# amp_kit_v02.net
KiCad netlist of a schematic drawn in EAGLE
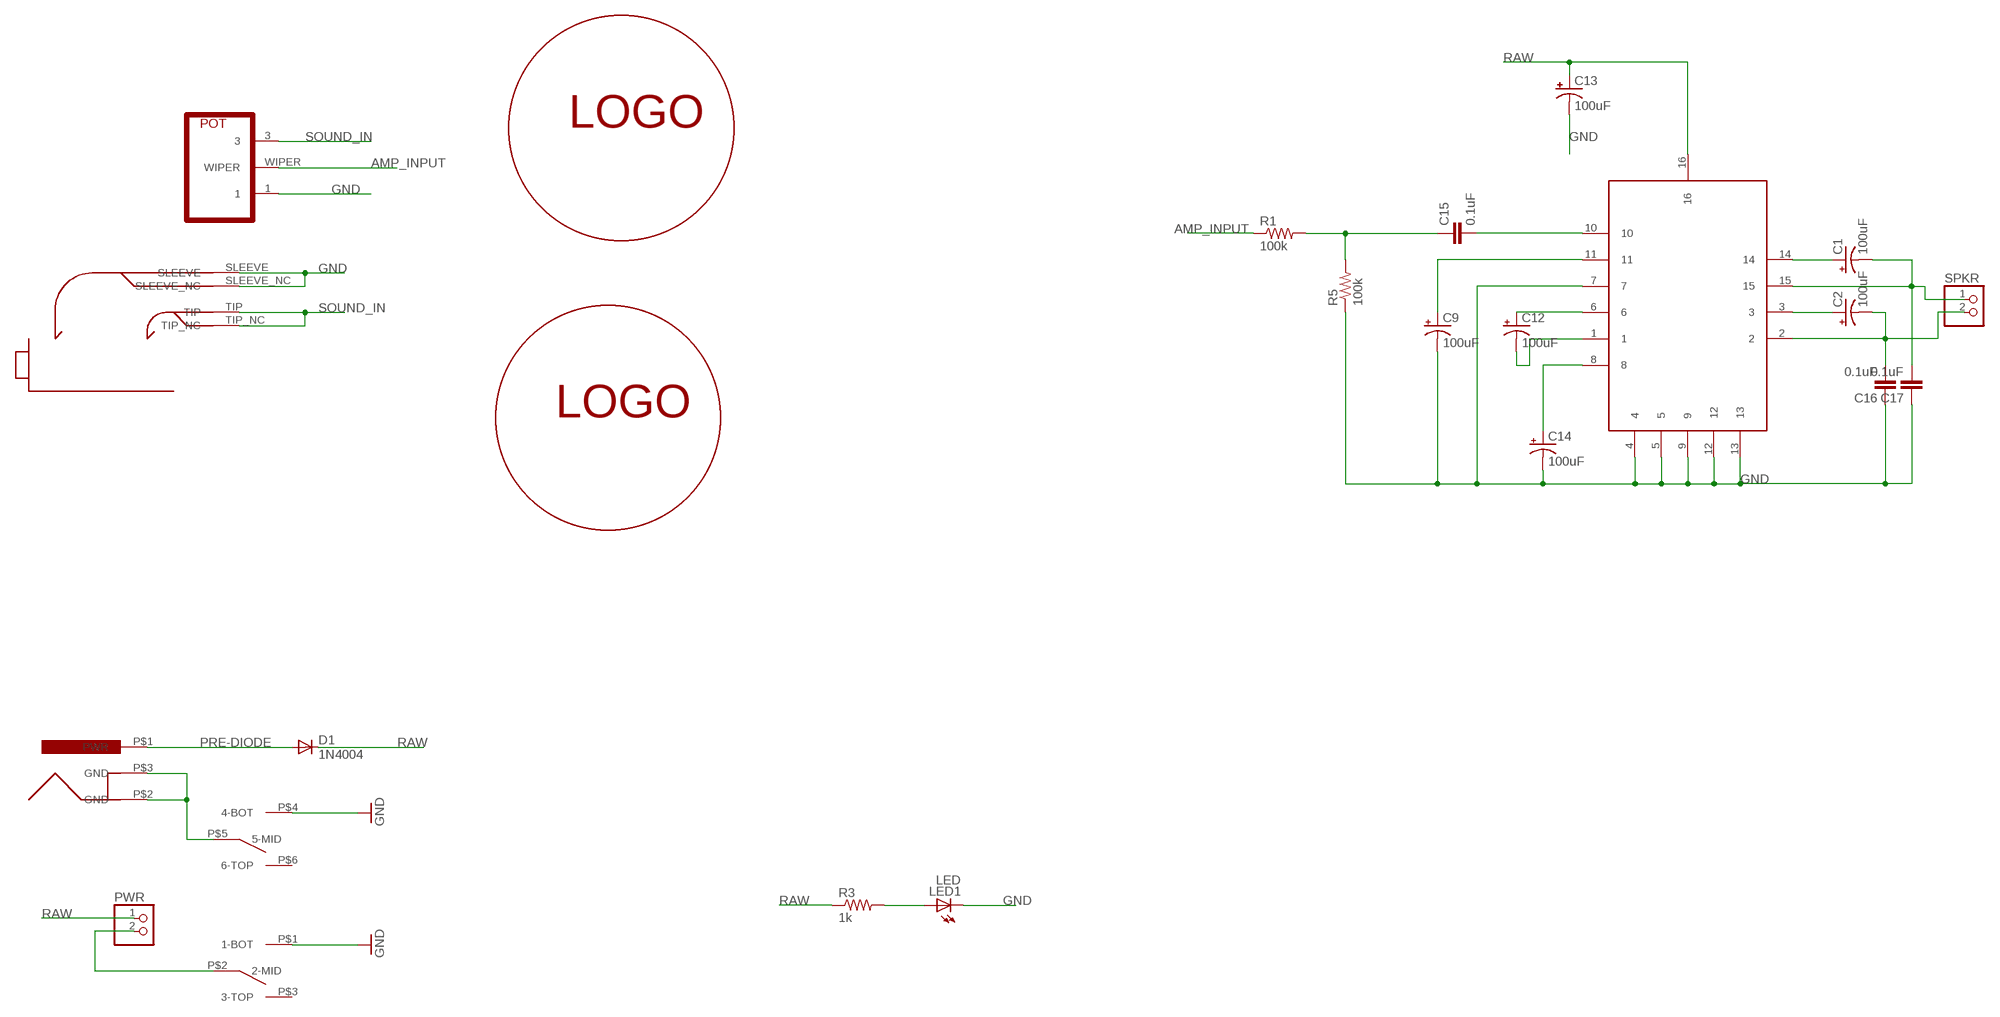
[diagram p0: schematic, sheet 1]

(export (version "E")
  (design (tool "Eeschema 10.0.6"))
  (components
    (comp (ref "C1")
      (value "100uF")
      (footprint "eagle-import:E2,5-7")
      (libsource (lib "eagle-import") (part "CPOL-USE2.5-7"))
    )
    (comp (ref "C2")
      (value "100uF")
      (footprint "eagle-import:E2,5-7")
      (libsource (lib "eagle-import") (part "CPOL-USE2.5-7"))
    )
    (comp (ref "C9")
      (value "100uF")
      (footprint "eagle-import:E2,5-7")
      (libsource (lib "eagle-import") (part "CPOL-USE2.5-7"))
    )
    (comp (ref "C12")
      (value "100uF")
      (footprint "eagle-import:E2,5-7")
      (libsource (lib "eagle-import") (part "CPOL-USE2.5-7"))
    )
    (comp (ref "C13")
      (value "100uF")
      (footprint "eagle-import:E2,5-7")
      (libsource (lib "eagle-import") (part "CPOL-USE2.5-7"))
    )
    (comp (ref "C14")
      (value "100uF")
      (footprint "eagle-import:E2,5-7")
      (libsource (lib "eagle-import") (part "CPOL-USE2.5-7"))
    )
    (comp (ref "C15")
      (value "0.1uF")
      (footprint "eagle-import:C025-025X050")
      (libsource (lib "eagle-import") (part "CAP025-025X050"))
    )
    (comp (ref "C16")
      (value "0.1uF")
      (footprint "eagle-import:C025-025X050")
      (libsource (lib "eagle-import") (part "CAP025-025X050"))
    )
    (comp (ref "C17")
      (value "0.1uF")
      (footprint "eagle-import:C025-025X050")
      (libsource (lib "eagle-import") (part "CAP025-025X050"))
    )
    (comp (ref "D1")
      (value "1N4004")
      (footprint "eagle-import:DO41-10")
      (libsource (lib "eagle-import") (part "1N4004"))
    )
    (comp (ref "LED1")
      (value "LED")
      (footprint "eagle-import:LED5MM")
      (libsource (lib "eagle-import") (part "LED5MM"))
    )
    (comp (ref "PWR")
      (value "PINHD-1X2")
      (footprint "eagle-import:1X02")
      (libsource (lib "eagle-import") (part "PINHD-1X2"))
    )
    (comp (ref "R1")
      (value "100k")
      (footprint "eagle-import:0204V")
      (libsource (lib "eagle-import") (part "R-US_0204/2V"))
    )
    (comp (ref "R3")
      (value "1k")
      (footprint "eagle-import:0207_10")
      (libsource (lib "eagle-import") (part "R-US_0207/10"))
    )
    (comp (ref "R5")
      (value "100k")
      (footprint "eagle-import:0204V")
      (libsource (lib "eagle-import") (part "R-US_0204/2V"))
    )
    (comp (ref "SPKR")
      (value "PINHD-1X2")
      (footprint "eagle-import:1X02")
      (libsource (lib "eagle-import") (part "PINHD-1X2"))
    )
    (comp (ref "U$1")
      (value "TEA2025")
      (footprint "eagle-import:DIL16")
      (libsource (lib "eagle-import") (part "TEA2025"))
    )
    (comp (ref "U$2")
      (value "LOGOCG")
      (footprint "eagle-import:LOGO-CG")
      (libsource (lib "eagle-import") (part "LOGOCG"))
    )
    (comp (ref "U$3")
      (value "POT_BOX_AMP")
      (footprint "eagle-import:POT_BOX_AMP")
      (libsource (lib "eagle-import") (part "POT_BOX_AMP"))
    )
    (comp (ref "U$4")
      (value "PUSHPOWER")
      (footprint "eagle-import:PUSHPOWER")
      (libsource (lib "eagle-import") (part "PUSHPOWER"))
    )
    (comp (ref "U$5")
      (value "POWER_JACK")
      (footprint "eagle-import:POWER_JACK")
      (libsource (lib "eagle-import") (part "POWER_JACK"))
    )
    (comp (ref "U$6")
      (value "MONO_PHONE")
      (footprint "eagle-import:MONO_PHONE")
      (libsource (lib "eagle-import") (part "MONO_PHONE"))
    )
    (comp (ref "U$7")
      (value "LOGOCG")
      (footprint "eagle-import:LOGO-CG")
      (libsource (lib "eagle-import") (part "LOGOCG"))
    )
  )
  (nets
    (net (code "1") (name "/AMP_INPUT") (class "Default")
      (node (ref "R1") (pin "1") (pinfunction "1_1") (pintype "passive"))
      (node (ref "U$3") (pin "WIPER") (pinfunction "WIPER_WIPER") (pintype "bidirectional"))
    )
    (net (code "2") (name "/PRE-DIODE") (class "Default")
      (node (ref "D1") (pin "A") (pinfunction "A_A") (pintype "passive"))
      (node (ref "U$5") (pin "P$1") (pinfunction "PWR_P$1") (pintype "bidirectional"))
    )
    (net (code "3") (name "/RAW") (class "Default")
      (node (ref "C13") (pin "+") (pinfunction "+_+") (pintype "passive"))
      (node (ref "D1") (pin "C") (pinfunction "C_C") (pintype "passive"))
      (node (ref "PWR") (pin "1") (pinfunction "1_1") (pintype "passive"))
      (node (ref "R3") (pin "1") (pinfunction "1_1") (pintype "passive"))
      (node (ref "U$1") (pin "16") (pinfunction "16_16") (pintype "bidirectional"))
    )
    (net (code "4") (name "/SOUND_IN") (class "Default")
      (node (ref "U$3") (pin "3") (pinfunction "3_3") (pintype "bidirectional"))
      (node (ref "U$6") (pin "TIP") (pinfunction "TIP_TIP") (pintype "bidirectional"))
      (node (ref "U$6") (pin "TIP_NC") (pinfunction "TIP_NC_TIP_NC") (pintype "bidirectional"))
    )
    (net (code "5") (name "GND") (class "Default")
      (node (ref "C13") (pin "-") (pinfunction "-_-") (pintype "passive"))
      (node (ref "C14") (pin "-") (pinfunction "-_-") (pintype "passive"))
      (node (ref "C16") (pin "1") (pinfunction "1_1") (pintype "passive"))
      (node (ref "C17") (pin "1") (pinfunction "1_1") (pintype "passive"))
      (node (ref "C9") (pin "-") (pinfunction "-_-") (pintype "passive"))
      (node (ref "LED1") (pin "K") (pinfunction "C_K") (pintype "passive"))
      (node (ref "R5") (pin "1") (pinfunction "1_1") (pintype "passive"))
      (node (ref "U$1") (pin "12") (pinfunction "12_12") (pintype "bidirectional"))
      (node (ref "U$1") (pin "13") (pinfunction "13_13") (pintype "bidirectional"))
      (node (ref "U$1") (pin "4") (pinfunction "4_4") (pintype "bidirectional"))
      (node (ref "U$1") (pin "5") (pinfunction "5_5") (pintype "bidirectional"))
      (node (ref "U$1") (pin "7") (pinfunction "7_7") (pintype "bidirectional"))
      (node (ref "U$1") (pin "9") (pinfunction "9_9") (pintype "bidirectional"))
      (node (ref "U$3") (pin "1") (pinfunction "1_1") (pintype "bidirectional"))
      (node (ref "U$4") (pin "P$1") (pinfunction "1-BOT_P$1") (pintype "bidirectional"))
      (node (ref "U$4") (pin "P$4") (pinfunction "4-BOT_P$4") (pintype "bidirectional"))
      (node (ref "U$6") (pin "SLEEVE") (pinfunction "SLEEVE_SLEEVE") (pintype "bidirectional"))
      (node (ref "U$6") (pin "SLEEVE_NC") (pinfunction "SLEEVE_NC_SLEEVE_NC") (pintype "bidirectional"))
    )
    (net (code "6") (name "Net-(C1-Pad+)") (class "Default")
      (node (ref "C1") (pin "+") (pinfunction "+_+") (pintype "passive"))
      (node (ref "U$1") (pin "14") (pinfunction "14_14") (pintype "bidirectional"))
    )
    (net (code "7") (name "Net-(C1-Pad-)") (class "Default")
      (node (ref "C1") (pin "-") (pinfunction "-_-") (pintype "passive"))
      (node (ref "C17") (pin "2") (pinfunction "2_2") (pintype "passive"))
      (node (ref "SPKR") (pin "1") (pinfunction "1_1") (pintype "passive"))
      (node (ref "U$1") (pin "15") (pinfunction "15_15") (pintype "bidirectional"))
    )
    (net (code "8") (name "Net-(C2-Pad+)") (class "Default")
      (node (ref "C2") (pin "+") (pinfunction "+_+") (pintype "passive"))
      (node (ref "U$1") (pin "3") (pinfunction "3_3") (pintype "bidirectional"))
    )
    (net (code "9") (name "Net-(C9-Pad+)") (class "Default")
      (node (ref "C9") (pin "+") (pinfunction "+_+") (pintype "passive"))
      (node (ref "U$1") (pin "11") (pinfunction "11_11") (pintype "bidirectional"))
    )
    (net (code "10") (name "Net-(C12-Pad+)") (class "Default")
      (node (ref "C12") (pin "+") (pinfunction "+_+") (pintype "passive"))
      (node (ref "U$1") (pin "6") (pinfunction "6_6") (pintype "bidirectional"))
    )
    (net (code "11") (name "Net-(C12-Pad-)") (class "Default")
      (node (ref "C12") (pin "-") (pinfunction "-_-") (pintype "passive"))
      (node (ref "U$1") (pin "1") (pinfunction "1_1") (pintype "bidirectional"))
    )
    (net (code "12") (name "Net-(C14-Pad+)") (class "Default")
      (node (ref "C14") (pin "+") (pinfunction "+_+") (pintype "passive"))
      (node (ref "U$1") (pin "8") (pinfunction "8_8") (pintype "bidirectional"))
    )
    (net (code "13") (name "Net-(C15-Pad1)") (class "Default")
      (node (ref "C15") (pin "1") (pinfunction "1_1") (pintype "passive"))
      (node (ref "R1") (pin "2") (pinfunction "2_2") (pintype "passive"))
      (node (ref "R5") (pin "2") (pinfunction "2_2") (pintype "passive"))
    )
    (net (code "14") (name "Net-(C15-Pad2)") (class "Default")
      (node (ref "C15") (pin "2") (pinfunction "2_2") (pintype "passive"))
      (node (ref "U$1") (pin "10") (pinfunction "10_10") (pintype "bidirectional"))
    )
    (net (code "15") (name "Net-(C16-Pad2)") (class "Default")
      (node (ref "C16") (pin "2") (pinfunction "2_2") (pintype "passive"))
      (node (ref "C2") (pin "-") (pinfunction "-_-") (pintype "passive"))
      (node (ref "SPKR") (pin "2") (pinfunction "2_2") (pintype "passive"))
      (node (ref "U$1") (pin "2") (pinfunction "2_2") (pintype "bidirectional"))
    )
    (net (code "16") (name "Net-(LED1-PadA)") (class "Default")
      (node (ref "LED1") (pin "A") (pinfunction "A_A") (pintype "passive"))
      (node (ref "R3") (pin "2") (pinfunction "2_2") (pintype "passive"))
    )
    (net (code "17") (name "Net-(U$4-2-MID)") (class "Default")
      (node (ref "PWR") (pin "2") (pinfunction "2_2") (pintype "passive"))
      (node (ref "U$4") (pin "P$2") (pinfunction "2-MID_P$2") (pintype "bidirectional"))
    )
    (net (code "18") (name "Net-(U$4-5-MID)") (class "Default")
      (node (ref "U$4") (pin "P$5") (pinfunction "5-MID_P$5") (pintype "bidirectional"))
      (node (ref "U$5") (pin "P$2") (pinfunction "GND_P$2") (pintype "bidirectional"))
      (node (ref "U$5") (pin "P$3") (pinfunction "GND_P$3") (pintype "bidirectional"))
    )
    (net (code "19") (name "unconnected-(U$4-3-TOP-PadP$3)") (class "Default")
      (node (ref "U$4") (pin "P$3") (pinfunction "3-TOP_P$3") (pintype "bidirectional"))
    )
    (net (code "20") (name "unconnected-(U$4-6-TOP-PadP$6)") (class "Default")
      (node (ref "U$4") (pin "P$6") (pinfunction "6-TOP_P$6") (pintype "bidirectional"))
    )
  )
)
